# EMMC.net
KiCad netlist of a schematic drawn in Altium Designer
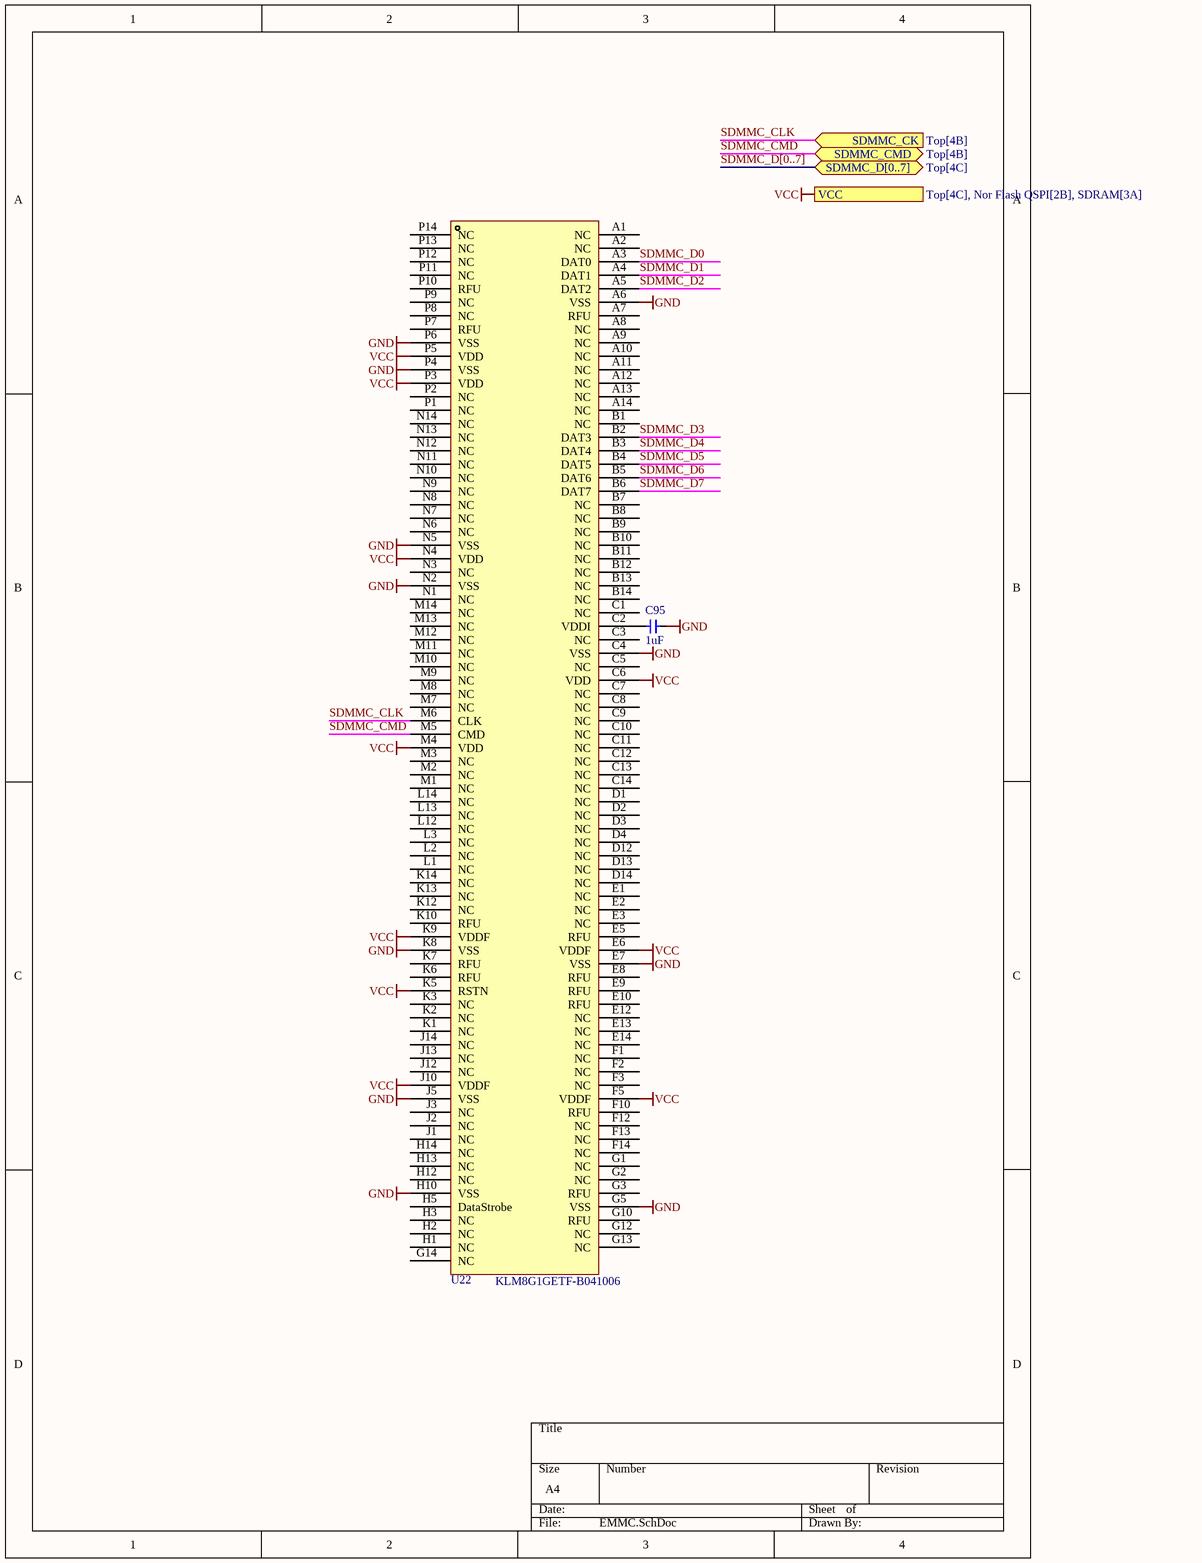
[diagram p0: EMMC.SchDoc]

(export (version "E")
  (design (tool "Eeschema 10.0.6"))
  (components
    (comp (ref "C95")
      (value "1uF")
      (footprint "0402-C")
      (description "Capacitor")
      (libsource (lib "MyPcbLib") (part "电容-0402"))
    )
    (comp (ref "U22")
      (value "KLM8G1GETF-B041006")
      (footprint "FBGA-153_L13.0-W11.5-P0.50_KLMAG1JETD-B041")
      (fields (field (name "MANUFACTURER") "SAMSUNG(三星半导体)"))
      (libsource (lib "MyLib") (part "KLM8G1GETF-B041006"))
    )
  )
  (nets
    (net (code "1") (name "/SDMMC_CLK") (class "Default")
      (node (ref "U22") (pin "M6") (pinfunction "CLK_M6") (pintype "passive"))
    )
    (net (code "2") (name "/SDMMC_CMD") (class "Default")
      (node (ref "U22") (pin "M5") (pinfunction "CMD_M5") (pintype "passive"))
    )
    (net (code "3") (name "/SDMMC_D0") (class "Default")
      (node (ref "U22") (pin "A3") (pinfunction "DAT0_A3") (pintype "passive"))
    )
    (net (code "4") (name "/SDMMC_D1") (class "Default")
      (node (ref "U22") (pin "A4") (pinfunction "DAT1_A4") (pintype "passive"))
    )
    (net (code "5") (name "/SDMMC_D2") (class "Default")
      (node (ref "U22") (pin "A5") (pinfunction "DAT2_A5") (pintype "passive"))
    )
    (net (code "6") (name "/SDMMC_D3") (class "Default")
      (node (ref "U22") (pin "B2") (pinfunction "DAT3_B2") (pintype "passive"))
    )
    (net (code "7") (name "/SDMMC_D4") (class "Default")
      (node (ref "U22") (pin "B3") (pinfunction "DAT4_B3") (pintype "passive"))
    )
    (net (code "8") (name "/SDMMC_D5") (class "Default")
      (node (ref "U22") (pin "B4") (pinfunction "DAT5_B4") (pintype "passive"))
    )
    (net (code "9") (name "/SDMMC_D6") (class "Default")
      (node (ref "U22") (pin "B5") (pinfunction "DAT6_B5") (pintype "passive"))
    )
    (net (code "10") (name "/SDMMC_D7") (class "Default")
      (node (ref "U22") (pin "B6") (pinfunction "DAT7_B6") (pintype "passive"))
    )
    (net (code "12") (name "GND") (class "Default")
      (node (ref "C95") (pin "2") (pinfunction "2_2") (pintype "passive"))
      (node (ref "U22") (pin "A6") (pinfunction "VSS_A6") (pintype "passive"))
      (node (ref "U22") (pin "C4") (pinfunction "VSS_C4") (pintype "passive"))
      (node (ref "U22") (pin "E7") (pinfunction "VSS_E7") (pintype "passive"))
      (node (ref "U22") (pin "G5") (pinfunction "VSS_G5") (pintype "passive"))
      (node (ref "U22") (pin "H10") (pinfunction "VSS_H10") (pintype "passive"))
      (node (ref "U22") (pin "J5") (pinfunction "VSS_J5") (pintype "passive"))
      (node (ref "U22") (pin "K8") (pinfunction "VSS_K8") (pintype "passive"))
      (node (ref "U22") (pin "N2") (pinfunction "VSS_N2") (pintype "passive"))
      (node (ref "U22") (pin "N5") (pinfunction "VSS_N5") (pintype "passive"))
      (node (ref "U22") (pin "P4") (pinfunction "VSS_P4") (pintype "passive"))
      (node (ref "U22") (pin "P6") (pinfunction "VSS_P6") (pintype "passive"))
    )
    (net (code "13") (name "Net-(U22-VDDI)") (class "Default")
      (node (ref "C95") (pin "1") (pinfunction "1_1") (pintype "passive"))
      (node (ref "U22") (pin "C2") (pinfunction "VDDI_C2") (pintype "passive"))
    )
    (net (code "14") (name "VCC") (class "Default")
      (node (ref "U22") (pin "C6") (pinfunction "VDD_C6") (pintype "passive"))
      (node (ref "U22") (pin "E6") (pinfunction "VDDF_E6") (pintype "passive"))
      (node (ref "U22") (pin "F5") (pinfunction "VDDF_F5") (pintype "passive"))
      (node (ref "U22") (pin "J10") (pinfunction "VDDF_J10") (pintype "passive"))
      (node (ref "U22") (pin "K5") (pinfunction "RSTN_K5") (pintype "passive"))
      (node (ref "U22") (pin "K9") (pinfunction "VDDF_K9") (pintype "passive"))
      (node (ref "U22") (pin "M4") (pinfunction "VDD_M4") (pintype "passive"))
      (node (ref "U22") (pin "N4") (pinfunction "VDD_N4") (pintype "passive"))
      (node (ref "U22") (pin "P3") (pinfunction "VDD_P3") (pintype "passive"))
      (node (ref "U22") (pin "P5") (pinfunction "VDD_P5") (pintype "passive"))
    )
    (net (code "15") (name "unconnected-(U22-DataStrobe-PadH5)") (class "Default")
      (node (ref "U22") (pin "H5") (pinfunction "DataStrobe_H5") (pintype "passive"))
    )
    (net (code "16") (name "unconnected-(U22-NC-PadA1)") (class "Default")
      (node (ref "U22") (pin "A1") (pinfunction "NC_A1") (pintype "passive"))
    )
    (net (code "17") (name "unconnected-(U22-NC-PadA2)") (class "Default")
      (node (ref "U22") (pin "A2") (pinfunction "NC_A2") (pintype "passive"))
    )
    (net (code "18") (name "unconnected-(U22-NC-PadA8)") (class "Default")
      (node (ref "U22") (pin "A8") (pinfunction "NC_A8") (pintype "passive"))
    )
    (net (code "19") (name "unconnected-(U22-NC-PadA9)") (class "Default")
      (node (ref "U22") (pin "A9") (pinfunction "NC_A9") (pintype "passive"))
    )
    (net (code "20") (name "unconnected-(U22-NC-PadA10)") (class "Default")
      (node (ref "U22") (pin "A10") (pinfunction "NC_A10") (pintype "passive"))
    )
    (net (code "21") (name "unconnected-(U22-NC-PadA11)") (class "Default")
      (node (ref "U22") (pin "A11") (pinfunction "NC_A11") (pintype "passive"))
    )
    (net (code "22") (name "unconnected-(U22-NC-PadA12)") (class "Default")
      (node (ref "U22") (pin "A12") (pinfunction "NC_A12") (pintype "passive"))
    )
    (net (code "23") (name "unconnected-(U22-NC-PadA13)") (class "Default")
      (node (ref "U22") (pin "A13") (pinfunction "NC_A13") (pintype "passive"))
    )
    (net (code "24") (name "unconnected-(U22-NC-PadA14)") (class "Default")
      (node (ref "U22") (pin "A14") (pinfunction "NC_A14") (pintype "passive"))
    )
    (net (code "25") (name "unconnected-(U22-NC-PadB1)") (class "Default")
      (node (ref "U22") (pin "B1") (pinfunction "NC_B1") (pintype "passive"))
    )
    (net (code "26") (name "unconnected-(U22-NC-PadB7)") (class "Default")
      (node (ref "U22") (pin "B7") (pinfunction "NC_B7") (pintype "passive"))
    )
    (net (code "27") (name "unconnected-(U22-NC-PadB8)") (class "Default")
      (node (ref "U22") (pin "B8") (pinfunction "NC_B8") (pintype "passive"))
    )
    (net (code "28") (name "unconnected-(U22-NC-PadB9)") (class "Default")
      (node (ref "U22") (pin "B9") (pinfunction "NC_B9") (pintype "passive"))
    )
    (net (code "29") (name "unconnected-(U22-NC-PadB10)") (class "Default")
      (node (ref "U22") (pin "B10") (pinfunction "NC_B10") (pintype "passive"))
    )
    (net (code "30") (name "unconnected-(U22-NC-PadB11)") (class "Default")
      (node (ref "U22") (pin "B11") (pinfunction "NC_B11") (pintype "passive"))
    )
    (net (code "31") (name "unconnected-(U22-NC-PadB12)") (class "Default")
      (node (ref "U22") (pin "B12") (pinfunction "NC_B12") (pintype "passive"))
    )
    (net (code "32") (name "unconnected-(U22-NC-PadB13)") (class "Default")
      (node (ref "U22") (pin "B13") (pinfunction "NC_B13") (pintype "passive"))
    )
    (net (code "33") (name "unconnected-(U22-NC-PadB14)") (class "Default")
      (node (ref "U22") (pin "B14") (pinfunction "NC_B14") (pintype "passive"))
    )
    (net (code "34") (name "unconnected-(U22-NC-PadC1)") (class "Default")
      (node (ref "U22") (pin "C1") (pinfunction "NC_C1") (pintype "passive"))
    )
    (net (code "35") (name "unconnected-(U22-NC-PadC3)") (class "Default")
      (node (ref "U22") (pin "C3") (pinfunction "NC_C3") (pintype "passive"))
    )
    (net (code "36") (name "unconnected-(U22-NC-PadC5)") (class "Default")
      (node (ref "U22") (pin "C5") (pinfunction "NC_C5") (pintype "passive"))
    )
    (net (code "37") (name "unconnected-(U22-NC-PadC7)") (class "Default")
      (node (ref "U22") (pin "C7") (pinfunction "NC_C7") (pintype "passive"))
    )
    (net (code "38") (name "unconnected-(U22-NC-PadC8)") (class "Default")
      (node (ref "U22") (pin "C8") (pinfunction "NC_C8") (pintype "passive"))
    )
    (net (code "39") (name "unconnected-(U22-NC-PadC9)") (class "Default")
      (node (ref "U22") (pin "C9") (pinfunction "NC_C9") (pintype "passive"))
    )
    (net (code "40") (name "unconnected-(U22-NC-PadC10)") (class "Default")
      (node (ref "U22") (pin "C10") (pinfunction "NC_C10") (pintype "passive"))
    )
    (net (code "41") (name "unconnected-(U22-NC-PadC11)") (class "Default")
      (node (ref "U22") (pin "C11") (pinfunction "NC_C11") (pintype "passive"))
    )
    (net (code "42") (name "unconnected-(U22-NC-PadC12)") (class "Default")
      (node (ref "U22") (pin "C12") (pinfunction "NC_C12") (pintype "passive"))
    )
    (net (code "43") (name "unconnected-(U22-NC-PadC13)") (class "Default")
      (node (ref "U22") (pin "C13") (pinfunction "NC_C13") (pintype "passive"))
    )
    (net (code "44") (name "unconnected-(U22-NC-PadC14)") (class "Default")
      (node (ref "U22") (pin "C14") (pinfunction "NC_C14") (pintype "passive"))
    )
    (net (code "45") (name "unconnected-(U22-NC-PadD1)") (class "Default")
      (node (ref "U22") (pin "D1") (pinfunction "NC_D1") (pintype "passive"))
    )
    (net (code "46") (name "unconnected-(U22-NC-PadD2)") (class "Default")
      (node (ref "U22") (pin "D2") (pinfunction "NC_D2") (pintype "passive"))
    )
    (net (code "47") (name "unconnected-(U22-NC-PadD3)") (class "Default")
      (node (ref "U22") (pin "D3") (pinfunction "NC_D3") (pintype "passive"))
    )
    (net (code "48") (name "unconnected-(U22-NC-PadD4)") (class "Default")
      (node (ref "U22") (pin "D4") (pinfunction "NC_D4") (pintype "passive"))
    )
    (net (code "49") (name "unconnected-(U22-NC-PadD12)") (class "Default")
      (node (ref "U22") (pin "D12") (pinfunction "NC_D12") (pintype "passive"))
    )
    (net (code "50") (name "unconnected-(U22-NC-PadD13)") (class "Default")
      (node (ref "U22") (pin "D13") (pinfunction "NC_D13") (pintype "passive"))
    )
    (net (code "51") (name "unconnected-(U22-NC-PadD14)") (class "Default")
      (node (ref "U22") (pin "D14") (pinfunction "NC_D14") (pintype "passive"))
    )
    (net (code "52") (name "unconnected-(U22-NC-PadE1)") (class "Default")
      (node (ref "U22") (pin "E1") (pinfunction "NC_E1") (pintype "passive"))
    )
    (net (code "53") (name "unconnected-(U22-NC-PadE2)") (class "Default")
      (node (ref "U22") (pin "E2") (pinfunction "NC_E2") (pintype "passive"))
    )
    (net (code "54") (name "unconnected-(U22-NC-PadE3)") (class "Default")
      (node (ref "U22") (pin "E3") (pinfunction "NC_E3") (pintype "passive"))
    )
    (net (code "55") (name "unconnected-(U22-NC-PadE12)") (class "Default")
      (node (ref "U22") (pin "E12") (pinfunction "NC_E12") (pintype "passive"))
    )
    (net (code "56") (name "unconnected-(U22-NC-PadE13)") (class "Default")
      (node (ref "U22") (pin "E13") (pinfunction "NC_E13") (pintype "passive"))
    )
    (net (code "57") (name "unconnected-(U22-NC-PadE14)") (class "Default")
      (node (ref "U22") (pin "E14") (pinfunction "NC_E14") (pintype "passive"))
    )
    (net (code "58") (name "unconnected-(U22-NC-PadF1)") (class "Default")
      (node (ref "U22") (pin "F1") (pinfunction "NC_F1") (pintype "passive"))
    )
    (net (code "59") (name "unconnected-(U22-NC-PadF2)") (class "Default")
      (node (ref "U22") (pin "F2") (pinfunction "NC_F2") (pintype "passive"))
    )
    (net (code "60") (name "unconnected-(U22-NC-PadF3)") (class "Default")
      (node (ref "U22") (pin "F3") (pinfunction "NC_F3") (pintype "passive"))
    )
    (net (code "61") (name "unconnected-(U22-NC-PadF12)") (class "Default")
      (node (ref "U22") (pin "F12") (pinfunction "NC_F12") (pintype "passive"))
    )
    (net (code "62") (name "unconnected-(U22-NC-PadF13)") (class "Default")
      (node (ref "U22") (pin "F13") (pinfunction "NC_F13") (pintype "passive"))
    )
    (net (code "63") (name "unconnected-(U22-NC-PadF14)") (class "Default")
      (node (ref "U22") (pin "F14") (pinfunction "NC_F14") (pintype "passive"))
    )
    (net (code "64") (name "unconnected-(U22-NC-PadG1)") (class "Default")
      (node (ref "U22") (pin "G1") (pinfunction "NC_G1") (pintype "passive"))
    )
    (net (code "65") (name "unconnected-(U22-NC-PadG2)") (class "Default")
      (node (ref "U22") (pin "G2") (pinfunction "NC_G2") (pintype "passive"))
    )
    (net (code "66") (name "unconnected-(U22-NC-PadG12)") (class "Default")
      (node (ref "U22") (pin "G12") (pinfunction "NC_G12") (pintype "passive"))
    )
    (net (code "67") (name "unconnected-(U22-NC-PadG13)") (class "Default")
      (node (ref "U22") (pin "G13") (pinfunction "NC_G13") (pintype "passive"))
    )
    (net (code "68") (name "unconnected-(U22-NC-PadG14)") (class "Default")
      (node (ref "U22") (pin "G14") (pinfunction "NC_G14") (pintype "passive"))
    )
    (net (code "69") (name "unconnected-(U22-NC-PadH1)") (class "Default")
      (node (ref "U22") (pin "H1") (pinfunction "NC_H1") (pintype "passive"))
    )
    (net (code "70") (name "unconnected-(U22-NC-PadH2)") (class "Default")
      (node (ref "U22") (pin "H2") (pinfunction "NC_H2") (pintype "passive"))
    )
    (net (code "71") (name "unconnected-(U22-NC-PadH3)") (class "Default")
      (node (ref "U22") (pin "H3") (pinfunction "NC_H3") (pintype "passive"))
    )
    (net (code "72") (name "unconnected-(U22-NC-PadH12)") (class "Default")
      (node (ref "U22") (pin "H12") (pinfunction "NC_H12") (pintype "passive"))
    )
    (net (code "73") (name "unconnected-(U22-NC-PadH13)") (class "Default")
      (node (ref "U22") (pin "H13") (pinfunction "NC_H13") (pintype "passive"))
    )
    (net (code "74") (name "unconnected-(U22-NC-PadH14)") (class "Default")
      (node (ref "U22") (pin "H14") (pinfunction "NC_H14") (pintype "passive"))
    )
    (net (code "75") (name "unconnected-(U22-NC-PadJ1)") (class "Default")
      (node (ref "U22") (pin "J1") (pinfunction "NC_J1") (pintype "passive"))
    )
    (net (code "76") (name "unconnected-(U22-NC-PadJ2)") (class "Default")
      (node (ref "U22") (pin "J2") (pinfunction "NC_J2") (pintype "passive"))
    )
    (net (code "77") (name "unconnected-(U22-NC-PadJ3)") (class "Default")
      (node (ref "U22") (pin "J3") (pinfunction "NC_J3") (pintype "passive"))
    )
    (net (code "78") (name "unconnected-(U22-NC-PadJ12)") (class "Default")
      (node (ref "U22") (pin "J12") (pinfunction "NC_J12") (pintype "passive"))
    )
    (net (code "79") (name "unconnected-(U22-NC-PadJ13)") (class "Default")
      (node (ref "U22") (pin "J13") (pinfunction "NC_J13") (pintype "passive"))
    )
    (net (code "80") (name "unconnected-(U22-NC-PadJ14)") (class "Default")
      (node (ref "U22") (pin "J14") (pinfunction "NC_J14") (pintype "passive"))
    )
    (net (code "81") (name "unconnected-(U22-NC-PadK1)") (class "Default")
      (node (ref "U22") (pin "K1") (pinfunction "NC_K1") (pintype "passive"))
    )
    (net (code "82") (name "unconnected-(U22-NC-PadK2)") (class "Default")
      (node (ref "U22") (pin "K2") (pinfunction "NC_K2") (pintype "passive"))
    )
    (net (code "83") (name "unconnected-(U22-NC-PadK3)") (class "Default")
      (node (ref "U22") (pin "K3") (pinfunction "NC_K3") (pintype "passive"))
    )
    (net (code "84") (name "unconnected-(U22-NC-PadK12)") (class "Default")
      (node (ref "U22") (pin "K12") (pinfunction "NC_K12") (pintype "passive"))
    )
    (net (code "85") (name "unconnected-(U22-NC-PadK13)") (class "Default")
      (node (ref "U22") (pin "K13") (pinfunction "NC_K13") (pintype "passive"))
    )
    (net (code "86") (name "unconnected-(U22-NC-PadK14)") (class "Default")
      (node (ref "U22") (pin "K14") (pinfunction "NC_K14") (pintype "passive"))
    )
    (net (code "87") (name "unconnected-(U22-NC-PadL1)") (class "Default")
      (node (ref "U22") (pin "L1") (pinfunction "NC_L1") (pintype "passive"))
    )
    (net (code "88") (name "unconnected-(U22-NC-PadL2)") (class "Default")
      (node (ref "U22") (pin "L2") (pinfunction "NC_L2") (pintype "passive"))
    )
    (net (code "89") (name "unconnected-(U22-NC-PadL3)") (class "Default")
      (node (ref "U22") (pin "L3") (pinfunction "NC_L3") (pintype "passive"))
    )
    (net (code "90") (name "unconnected-(U22-NC-PadL12)") (class "Default")
      (node (ref "U22") (pin "L12") (pinfunction "NC_L12") (pintype "passive"))
    )
    (net (code "91") (name "unconnected-(U22-NC-PadL13)") (class "Default")
      (node (ref "U22") (pin "L13") (pinfunction "NC_L13") (pintype "passive"))
    )
    (net (code "92") (name "unconnected-(U22-NC-PadL14)") (class "Default")
      (node (ref "U22") (pin "L14") (pinfunction "NC_L14") (pintype "passive"))
    )
    (net (code "93") (name "unconnected-(U22-NC-PadM1)") (class "Default")
      (node (ref "U22") (pin "M1") (pinfunction "NC_M1") (pintype "passive"))
    )
    (net (code "94") (name "unconnected-(U22-NC-PadM2)") (class "Default")
      (node (ref "U22") (pin "M2") (pinfunction "NC_M2") (pintype "passive"))
    )
    (net (code "95") (name "unconnected-(U22-NC-PadM3)") (class "Default")
      (node (ref "U22") (pin "M3") (pinfunction "NC_M3") (pintype "passive"))
    )
    (net (code "96") (name "unconnected-(U22-NC-PadM7)") (class "Default")
      (node (ref "U22") (pin "M7") (pinfunction "NC_M7") (pintype "passive"))
    )
    (net (code "97") (name "unconnected-(U22-NC-PadM8)") (class "Default")
      (node (ref "U22") (pin "M8") (pinfunction "NC_M8") (pintype "passive"))
    )
    (net (code "98") (name "unconnected-(U22-NC-PadM9)") (class "Default")
      (node (ref "U22") (pin "M9") (pinfunction "NC_M9") (pintype "passive"))
    )
    (net (code "99") (name "unconnected-(U22-NC-PadM10)") (class "Default")
      (node (ref "U22") (pin "M10") (pinfunction "NC_M10") (pintype "passive"))
    )
    (net (code "100") (name "unconnected-(U22-NC-PadM11)") (class "Default")
      (node (ref "U22") (pin "M11") (pinfunction "NC_M11") (pintype "passive"))
    )
    (net (code "101") (name "unconnected-(U22-NC-PadM12)") (class "Default")
      (node (ref "U22") (pin "M12") (pinfunction "NC_M12") (pintype "passive"))
    )
    (net (code "102") (name "unconnected-(U22-NC-PadM13)") (class "Default")
      (node (ref "U22") (pin "M13") (pinfunction "NC_M13") (pintype "passive"))
    )
    (net (code "103") (name "unconnected-(U22-NC-PadM14)") (class "Default")
      (node (ref "U22") (pin "M14") (pinfunction "NC_M14") (pintype "passive"))
    )
    (net (code "104") (name "unconnected-(U22-NC-PadN1)") (class "Default")
      (node (ref "U22") (pin "N1") (pinfunction "NC_N1") (pintype "passive"))
    )
    (net (code "105") (name "unconnected-(U22-NC-PadN3)") (class "Default")
      (node (ref "U22") (pin "N3") (pinfunction "NC_N3") (pintype "passive"))
    )
    (net (code "106") (name "unconnected-(U22-NC-PadN6)") (class "Default")
      (node (ref "U22") (pin "N6") (pinfunction "NC_N6") (pintype "passive"))
    )
    (net (code "107") (name "unconnected-(U22-NC-PadN7)") (class "Default")
      (node (ref "U22") (pin "N7") (pinfunction "NC_N7") (pintype "passive"))
    )
    (net (code "108") (name "unconnected-(U22-NC-PadN8)") (class "Default")
      (node (ref "U22") (pin "N8") (pinfunction "NC_N8") (pintype "passive"))
    )
    (net (code "109") (name "unconnected-(U22-NC-PadN9)") (class "Default")
      (node (ref "U22") (pin "N9") (pinfunction "NC_N9") (pintype "passive"))
    )
    (net (code "110") (name "unconnected-(U22-NC-PadN10)") (class "Default")
      (node (ref "U22") (pin "N10") (pinfunction "NC_N10") (pintype "passive"))
    )
    (net (code "111") (name "unconnected-(U22-NC-PadN11)") (class "Default")
      (node (ref "U22") (pin "N11") (pinfunction "NC_N11") (pintype "passive"))
    )
    (net (code "112") (name "unconnected-(U22-NC-PadN12)") (class "Default")
      (node (ref "U22") (pin "N12") (pinfunction "NC_N12") (pintype "passive"))
    )
    (net (code "113") (name "unconnected-(U22-NC-PadN13)") (class "Default")
      (node (ref "U22") (pin "N13") (pinfunction "NC_N13") (pintype "passive"))
    )
    (net (code "114") (name "unconnected-(U22-NC-PadN14)") (class "Default")
      (node (ref "U22") (pin "N14") (pinfunction "NC_N14") (pintype "passive"))
    )
    (net (code "115") (name "unconnected-(U22-NC-PadP1)") (class "Default")
      (node (ref "U22") (pin "P1") (pinfunction "NC_P1") (pintype "passive"))
    )
    (net (code "116") (name "unconnected-(U22-NC-PadP2)") (class "Default")
      (node (ref "U22") (pin "P2") (pinfunction "NC_P2") (pintype "passive"))
    )
    (net (code "117") (name "unconnected-(U22-NC-PadP8)") (class "Default")
      (node (ref "U22") (pin "P8") (pinfunction "NC_P8") (pintype "passive"))
    )
    (net (code "118") (name "unconnected-(U22-NC-PadP9)") (class "Default")
      (node (ref "U22") (pin "P9") (pinfunction "NC_P9") (pintype "passive"))
    )
    (net (code "119") (name "unconnected-(U22-NC-PadP11)") (class "Default")
      (node (ref "U22") (pin "P11") (pinfunction "NC_P11") (pintype "passive"))
    )
    (net (code "120") (name "unconnected-(U22-NC-PadP12)") (class "Default")
      (node (ref "U22") (pin "P12") (pinfunction "NC_P12") (pintype "passive"))
    )
    (net (code "121") (name "unconnected-(U22-NC-PadP13)") (class "Default")
      (node (ref "U22") (pin "P13") (pinfunction "NC_P13") (pintype "passive"))
    )
    (net (code "122") (name "unconnected-(U22-NC-PadP14)") (class "Default")
      (node (ref "U22") (pin "P14") (pinfunction "NC_P14") (pintype "passive"))
    )
    (net (code "123") (name "unconnected-(U22-RFU-PadA7)") (class "Default")
      (node (ref "U22") (pin "A7") (pinfunction "RFU_A7") (pintype "passive"))
    )
    (net (code "124") (name "unconnected-(U22-RFU-PadE5)") (class "Default")
      (node (ref "U22") (pin "E5") (pinfunction "RFU_E5") (pintype "passive"))
    )
    (net (code "125") (name "unconnected-(U22-RFU-PadE8)") (class "Default")
      (node (ref "U22") (pin "E8") (pinfunction "RFU_E8") (pintype "passive"))
    )
    (net (code "126") (name "unconnected-(U22-RFU-PadE9)") (class "Default")
      (node (ref "U22") (pin "E9") (pinfunction "RFU_E9") (pintype "passive"))
    )
    (net (code "127") (name "unconnected-(U22-RFU-PadE10)") (class "Default")
      (node (ref "U22") (pin "E10") (pinfunction "RFU_E10") (pintype "passive"))
    )
    (net (code "128") (name "unconnected-(U22-RFU-PadF10)") (class "Default")
      (node (ref "U22") (pin "F10") (pinfunction "RFU_F10") (pintype "passive"))
    )
    (net (code "129") (name "unconnected-(U22-RFU-PadG3)") (class "Default")
      (node (ref "U22") (pin "G3") (pinfunction "RFU_G3") (pintype "passive"))
    )
    (net (code "130") (name "unconnected-(U22-RFU-PadG10)") (class "Default")
      (node (ref "U22") (pin "G10") (pinfunction "RFU_G10") (pintype "passive"))
    )
    (net (code "131") (name "unconnected-(U22-RFU-PadK6)") (class "Default")
      (node (ref "U22") (pin "K6") (pinfunction "RFU_K6") (pintype "passive"))
    )
    (net (code "132") (name "unconnected-(U22-RFU-PadK7)") (class "Default")
      (node (ref "U22") (pin "K7") (pinfunction "RFU_K7") (pintype "passive"))
    )
    (net (code "133") (name "unconnected-(U22-RFU-PadK10)") (class "Default")
      (node (ref "U22") (pin "K10") (pinfunction "RFU_K10") (pintype "passive"))
    )
    (net (code "134") (name "unconnected-(U22-RFU-PadP7)") (class "Default")
      (node (ref "U22") (pin "P7") (pinfunction "RFU_P7") (pintype "passive"))
    )
    (net (code "135") (name "unconnected-(U22-RFU-PadP10)") (class "Default")
      (node (ref "U22") (pin "P10") (pinfunction "RFU_P10") (pintype "passive"))
    )
  )
)
